# arduino_humidity_sensing.net
KiCad netlist of a schematic drawn in EAGLE
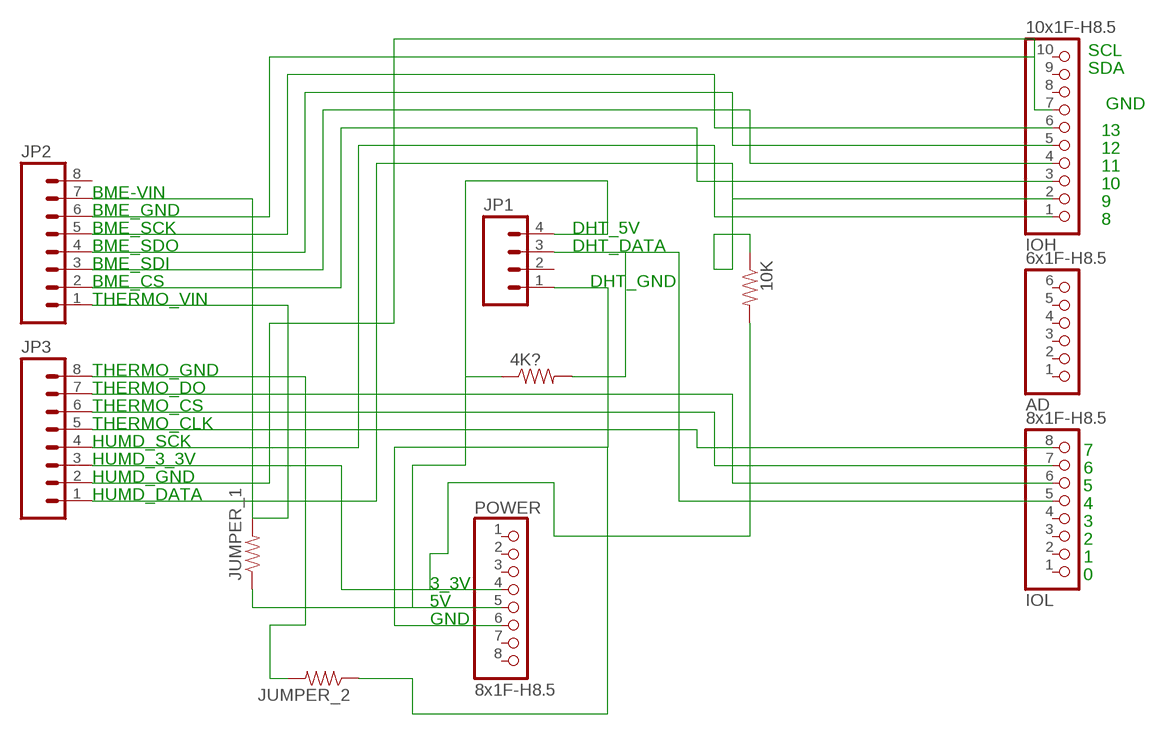
[diagram p0: schematic, sheet 1]

(export (version "E")
  (design (tool "Eeschema 10.0.6"))
  (components
    (comp (ref "4K?")
      (value "RESISTORPTH-1/2W")
      (footprint "eagle-import:AXIAL-0.5")
      (libsource (lib "eagle-import") (part "RESISTORPTH-1/2W"))
    )
    (comp (ref "10K")
      (value "RESISTORKIT")
      (footprint "eagle-import:AXIAL-0.3-KIT")
      (libsource (lib "eagle-import") (part "RESISTORKIT"))
    )
    (comp (ref "AD")
      (value "6x1F-H8.5")
      (footprint "eagle-import:1X06")
      (libsource (lib "eagle-import") (part "PINHD-1X6"))
    )
    (comp (ref "IOH")
      (value "10x1F-H8.5")
      (footprint "eagle-import:1X10")
      (libsource (lib "eagle-import") (part "PINHD-1X10_ARD"))
    )
    (comp (ref "IOL")
      (value "8x1F-H8.5")
      (footprint "eagle-import:1X08")
      (libsource (lib "eagle-import") (part "PINHD-1X8"))
    )
    (comp (ref "JP1")
      (value "M04PTH")
      (footprint "eagle-import:1X04")
      (libsource (lib "eagle-import") (part "M04PTH"))
    )
    (comp (ref "JP2")
      (value "M08NO_SILK")
      (footprint "eagle-import:1X08_NO_SILK")
      (libsource (lib "eagle-import") (part "M08NO_SILK"))
    )
    (comp (ref "JP3")
      (value "M08NO_SILK")
      (footprint "eagle-import:1X08_NO_SILK")
      (libsource (lib "eagle-import") (part "M08NO_SILK"))
    )
    (comp (ref "JUMPER_1")
      (value "RESISTORKIT")
      (footprint "eagle-import:AXIAL-0.3-KIT")
      (libsource (lib "eagle-import") (part "RESISTORKIT"))
    )
    (comp (ref "JUMPER_2")
      (value "RESISTORKIT")
      (footprint "eagle-import:AXIAL-0.3-KIT")
      (libsource (lib "eagle-import") (part "RESISTORKIT"))
    )
    (comp (ref "POWER")
      (value "8x1F-H8.5")
      (footprint "eagle-import:1X08")
      (libsource (lib "eagle-import") (part "PINHD-1X8"))
    )
  )
  (nets
    (net (code "1") (name "Net-(10K-1)") (class "Default")
      (node (ref "10K") (pin "P$1") (pinfunction "1_P$1") (pintype "passive"))
      (node (ref "IOH") (pin "2") (pinfunction "2_2") (pintype "passive"))
      (node (ref "JP3") (pin "1") (pinfunction "1_1") (pintype "passive"))
    )
    (net (code "2") (name "Net-(10K-2)") (class "Default")
      (node (ref "10K") (pin "P$2") (pinfunction "2_P$2") (pintype "passive"))
      (node (ref "JP3") (pin "3") (pinfunction "3_3") (pintype "passive"))
      (node (ref "POWER") (pin "4") (pinfunction "4_4") (pintype "passive"))
    )
    (net (code "3") (name "Net-(IOH-Pad1)") (class "Default")
      (node (ref "IOH") (pin "1") (pinfunction "1_1") (pintype "passive"))
      (node (ref "JP3") (pin "4") (pinfunction "4_4") (pintype "passive"))
    )
    (net (code "4") (name "Net-(IOH-Pad3)") (class "Default")
      (node (ref "IOH") (pin "3") (pinfunction "3_3") (pintype "passive"))
      (node (ref "JP2") (pin "2") (pinfunction "2_2") (pintype "passive"))
    )
    (net (code "5") (name "Net-(IOH-Pad4)") (class "Default")
      (node (ref "IOH") (pin "4") (pinfunction "4_4") (pintype "passive"))
      (node (ref "JP2") (pin "3") (pinfunction "3_3") (pintype "passive"))
    )
    (net (code "6") (name "Net-(IOH-Pad5)") (class "Default")
      (node (ref "IOH") (pin "5") (pinfunction "5_5") (pintype "passive"))
      (node (ref "JP2") (pin "4") (pinfunction "4_4") (pintype "passive"))
    )
    (net (code "7") (name "Net-(IOH-Pad6)") (class "Default")
      (node (ref "IOH") (pin "6") (pinfunction "6_6") (pintype "passive"))
      (node (ref "JP2") (pin "5") (pinfunction "5_5") (pintype "passive"))
    )
    (net (code "8") (name "Net-(IOH-Pad7)") (class "Default")
      (node (ref "IOH") (pin "7") (pinfunction "7_7") (pintype "passive"))
      (node (ref "JP2") (pin "6") (pinfunction "6_6") (pintype "passive"))
      (node (ref "JP3") (pin "2") (pinfunction "2_2") (pintype "passive"))
    )
    (net (code "9") (name "Net-(IOL-Pad5)") (class "Default")
      (node (ref "4K?") (pin "P$2") (pinfunction "2_P$2") (pintype "passive"))
      (node (ref "IOL") (pin "5") (pinfunction "5_5") (pintype "passive"))
      (node (ref "JP1") (pin "3") (pinfunction "3_3") (pintype "passive"))
    )
    (net (code "10") (name "Net-(IOL-Pad6)") (class "Default")
      (node (ref "IOL") (pin "6") (pinfunction "6_6") (pintype "passive"))
      (node (ref "JP3") (pin "7") (pinfunction "7_7") (pintype "passive"))
    )
    (net (code "11") (name "Net-(IOL-Pad7)") (class "Default")
      (node (ref "IOL") (pin "7") (pinfunction "7_7") (pintype "passive"))
      (node (ref "JP3") (pin "6") (pinfunction "6_6") (pintype "passive"))
    )
    (net (code "12") (name "Net-(IOL-Pad8)") (class "Default")
      (node (ref "IOL") (pin "8") (pinfunction "8_8") (pintype "passive"))
      (node (ref "JP3") (pin "5") (pinfunction "5_5") (pintype "passive"))
    )
    (net (code "13") (name "Net-(JUMPER_1-1)") (class "Default")
      (node (ref "4K?") (pin "P$1") (pinfunction "1_P$1") (pintype "passive"))
      (node (ref "JP1") (pin "4") (pinfunction "4_4") (pintype "passive"))
      (node (ref "JUMPER_1") (pin "P$1") (pinfunction "1_P$1") (pintype "passive"))
      (node (ref "POWER") (pin "5") (pinfunction "5_5") (pintype "passive"))
    )
    (net (code "14") (name "Net-(JUMPER_1-2)") (class "Default")
      (node (ref "JP2") (pin "1") (pinfunction "1_1") (pintype "passive"))
      (node (ref "JP2") (pin "7") (pinfunction "7_7") (pintype "passive"))
      (node (ref "JUMPER_1") (pin "P$2") (pinfunction "2_P$2") (pintype "passive"))
    )
    (net (code "15") (name "Net-(JUMPER_2-1)") (class "Default")
      (node (ref "JP1") (pin "1") (pinfunction "1_1") (pintype "passive"))
      (node (ref "JUMPER_2") (pin "P$1") (pinfunction "1_P$1") (pintype "passive"))
      (node (ref "POWER") (pin "6") (pinfunction "6_6") (pintype "passive"))
    )
    (net (code "16") (name "Net-(JUMPER_2-2)") (class "Default")
      (node (ref "JP3") (pin "8") (pinfunction "8_8") (pintype "passive"))
      (node (ref "JUMPER_2") (pin "P$2") (pinfunction "2_P$2") (pintype "passive"))
    )
    (net (code "17") (name "unconnected-(AD-Pad1)") (class "Default")
      (node (ref "AD") (pin "1") (pinfunction "1_1") (pintype "passive"))
    )
    (net (code "18") (name "unconnected-(AD-Pad2)") (class "Default")
      (node (ref "AD") (pin "2") (pinfunction "2_2") (pintype "passive"))
    )
    (net (code "19") (name "unconnected-(AD-Pad3)") (class "Default")
      (node (ref "AD") (pin "3") (pinfunction "3_3") (pintype "passive"))
    )
    (net (code "20") (name "unconnected-(AD-Pad4)") (class "Default")
      (node (ref "AD") (pin "4") (pinfunction "4_4") (pintype "passive"))
    )
    (net (code "21") (name "unconnected-(AD-Pad5)") (class "Default")
      (node (ref "AD") (pin "5") (pinfunction "5_5") (pintype "passive"))
    )
    (net (code "22") (name "unconnected-(AD-Pad6)") (class "Default")
      (node (ref "AD") (pin "6") (pinfunction "6_6") (pintype "passive"))
    )
    (net (code "23") (name "unconnected-(IOH-Pad8)") (class "Default")
      (node (ref "IOH") (pin "8") (pinfunction "8_8") (pintype "passive"))
    )
    (net (code "24") (name "unconnected-(IOH-Pad9)") (class "Default")
      (node (ref "IOH") (pin "9") (pinfunction "9_9") (pintype "passive"))
    )
    (net (code "25") (name "unconnected-(IOH-Pad10)") (class "Default")
      (node (ref "IOH") (pin "10") (pinfunction "10_10") (pintype "passive"))
    )
    (net (code "26") (name "unconnected-(IOL-Pad1)") (class "Default")
      (node (ref "IOL") (pin "1") (pinfunction "1_1") (pintype "passive"))
    )
    (net (code "27") (name "unconnected-(IOL-Pad2)") (class "Default")
      (node (ref "IOL") (pin "2") (pinfunction "2_2") (pintype "passive"))
    )
    (net (code "28") (name "unconnected-(IOL-Pad3)") (class "Default")
      (node (ref "IOL") (pin "3") (pinfunction "3_3") (pintype "passive"))
    )
    (net (code "29") (name "unconnected-(IOL-Pad4)") (class "Default")
      (node (ref "IOL") (pin "4") (pinfunction "4_4") (pintype "passive"))
    )
    (net (code "30") (name "unconnected-(JP1-Pad2)") (class "Default")
      (node (ref "JP1") (pin "2") (pinfunction "2_2") (pintype "passive"))
    )
    (net (code "31") (name "unconnected-(JP2-Pad8)") (class "Default")
      (node (ref "JP2") (pin "8") (pinfunction "8_8") (pintype "passive"))
    )
    (net (code "32") (name "unconnected-(POWER-Pad1)") (class "Default")
      (node (ref "POWER") (pin "1") (pinfunction "1_1") (pintype "passive"))
    )
    (net (code "33") (name "unconnected-(POWER-Pad2)") (class "Default")
      (node (ref "POWER") (pin "2") (pinfunction "2_2") (pintype "passive"))
    )
    (net (code "34") (name "unconnected-(POWER-Pad3)") (class "Default")
      (node (ref "POWER") (pin "3") (pinfunction "3_3") (pintype "passive"))
    )
    (net (code "35") (name "unconnected-(POWER-Pad7)") (class "Default")
      (node (ref "POWER") (pin "7") (pinfunction "7_7") (pintype "passive"))
    )
    (net (code "36") (name "unconnected-(POWER-Pad8)") (class "Default")
      (node (ref "POWER") (pin "8") (pinfunction "8_8") (pintype "passive"))
    )
  )
)
